# MainDuasRodas.net
KiCad netlist of a schematic drawn in Altium Designer
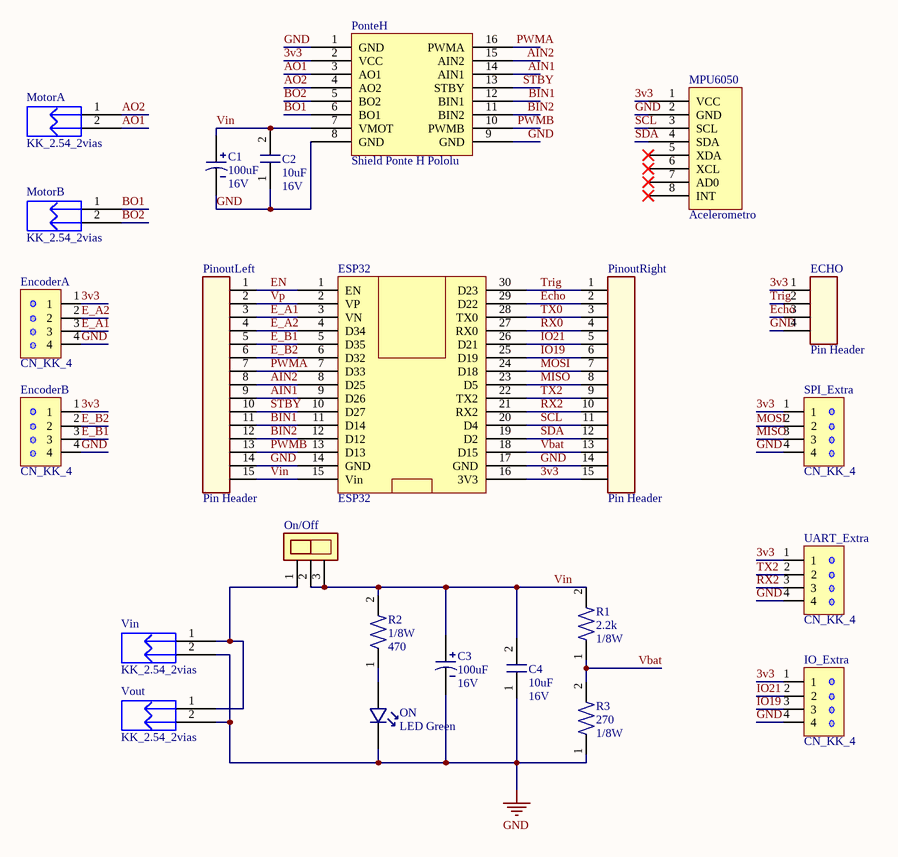
[diagram p0: MainDuasRodas.SchDoc]

(export (version "E")
  (design (tool "Eeschema 10.0.6"))
  (components
    (comp (ref "C1")
      (value "Cap Elec 100uF/16V")
      (footprint "Cap Elec 100uF/16V")
      (description "100µF 16V Aluminum Electrolytic Capacitors Radial")
      (fields (field (name "CAPACITANCE") "100uF") (field (name "VOLTAGE") "16V"))
      (libsource (lib "Capacitor Electrolytic PTH") (part "Cap Elec 100uF/16V"))
    )
    (comp (ref "C2")
      (value "CAP 10uF/16v")
      (footprint "CAP 10uF/16V")
      (description "10µF ±10% 16V Ceramic Capacitor X5R 0805 (2012 Metric)")
      (fields (field (name "CAPACITANCE") "10uF") (field (name "VOLTAGE") "16V"))
      (libsource (lib "Ceramic Capacitors 0805 16V") (part "CAP 10uF/16V"))
    )
    (comp (ref "C3")
      (value "Cap Elec 100uF/16V")
      (footprint "Cap Elec 100uF/16V")
      (description "100µF 16V Aluminum Electrolytic Capacitors Radial")
      (fields (field (name "CAPACITANCE") "100uF") (field (name "VOLTAGE") "16V"))
      (libsource (lib "Capacitor Electrolytic PTH") (part "Cap Elec 100uF/16V"))
    )
    (comp (ref "C4")
      (value "CAP 10uF/16v")
      (footprint "CAP 10uF/16V")
      (description "10µF ±10% 16V Ceramic Capacitor X5R 0805 (2012 Metric)")
      (fields (field (name "CAPACITANCE") "10uF") (field (name "VOLTAGE") "16V"))
      (libsource (lib "Ceramic Capacitors 0805 16V") (part "CAP 10uF/16V"))
    )
    (comp (ref "ECHO")
      (value "Pin Header")
      (footprint "Pin Header 4 Ways")
      (description "Connector Header PTH 0.100\" (2.54mm)")
      (libsource (lib "Connectors") (part "Pin Header 4 ways"))
    )
    (comp (ref "EncoderA")
      (value "CN_KK_4")
      (footprint "CN_KK_4_5045-4")
      (description "KK_4")
      (libsource (lib "") (part "CN_KK_4_1"))
    )
    (comp (ref "EncoderB")
      (value "CN_KK_4")
      (footprint "CN_KK_4_5045-4")
      (description "KK_4")
      (libsource (lib "") (part "CN_KK_4_1"))
    )
    (comp (ref "ESP32")
      (value "ESP32")
      (footprint "DIP30 - duplicate3")
      (libsource (lib "ESP32_NodeMCU") (part "ESP32"))
    )
    (comp (ref "IO_Extra")
      (value "CN_KK_4")
      (footprint "CN_KK_4_5045-4")
      (description "KK_4")
      (libsource (lib "i9Library_Altium") (part "CN_KK_4"))
    )
    (comp (ref "MotorA")
      (value "KK_2.54_2vias")
      (footprint "KK_2VIAS_180º")
      (description "Conector KK 2.54mm 2 vias")
      (libsource (lib "Altium_Library_Brasil") (part "KK_2.54_2vias"))
    )
    (comp (ref "MotorB")
      (value "KK_2.54_2vias")
      (footprint "KK_2VIAS_180º")
      (description "Conector KK 2.54mm 2 vias")
      (libsource (lib "Altium_Library_Brasil") (part "KK_2.54_2vias"))
    )
    (comp (ref "MPU6050")
      (value "Acelerometro")
      (footprint "MPU6050")
      (libsource (lib "MPU6050") (part "MPU6050"))
    )
    (comp (ref "ON")
      (value "LED Green")
      (footprint "LED GREEN PTH STAND")
      (description "Green 527nm LED Indication - Discrete 3.2V Radial")
      (libsource (lib "LEDs") (part "LED Green PTH Stand"))
    )
    (comp (ref "On/Off")
      (value "SS12D00G4")
      (footprint "SS12D00G4")
      (libsource (lib "Buttons & Switches") (part "SS12D00G4"))
    )
    (comp (ref "PinoutLeft")
      (value "Pin Header")
      (footprint "Pin Header 15 Ways")
      (description "Connector Header PTH 0.100\" (2.54mm)")
      (libsource (lib "Connectors") (part "Pin Header 15 ways"))
    )
    (comp (ref "PinoutRight")
      (value "Pin Header")
      (footprint "Pin Header 15 Ways")
      (description "Connector Header PTH 0.100\" (2.54mm)")
      (libsource (lib "") (part "Pin Header 15 ways_1"))
    )
    (comp (ref "PonteH")
      (value "Shield Ponte H Pololu")
      (footprint "SHIELDMD08AR")
      (libsource (lib "md08a2") (part "Md08a"))
    )
    (comp (ref "R1")
      (value "RES 0805")
      (footprint "RES SMD 2.2k OHM 1% 1/8W 0805")
      (description "2.2 kOhms ±1% 0.125W, 1/8W Chip Resistor 0805 (2012 Metric) Moisture Resistant Thick Film")
      (fields (field (name "RESISTENCE") "2.2k") (field (name "POWER") "1/8W"))
      (libsource (lib "Resistors 0805") (part "RES 2.2k 1% 1/8W"))
    )
    (comp (ref "R2")
      (value "RES 0805")
      (footprint "RES SMD 470OHM 1% 1/8W 0805")
      (description "470 Ohms ±1% 0.125W, 1/8W Chip Resistor 0805 (2012 Metric) Moisture Resistant Thick Film")
      (fields (field (name "POWER") "1/8W") (field (name "RESISTENCE") "470"))
      (libsource (lib "Resistors 0805") (part "RES 470 1% 1/8W"))
    )
    (comp (ref "R3")
      (value "RES 0805")
      (footprint "RES SMD 270 OHM 1% 1/8W 0805")
      (description "270Ohms ±1% 0.125W, 1/8W Chip Resistor 0805 (2012 Metric) Moisture Resistant Thick Film")
      (fields (field (name "RESISTENCE") "270") (field (name "POWER") "1/8W"))
      (libsource (lib "Resistors 0805") (part "RES 270 1% 1/8W"))
    )
    (comp (ref "SPI_Extra")
      (value "CN_KK_4")
      (footprint "CN_KK_4_5045-4")
      (description "KK_4")
      (libsource (lib "i9Library_Altium") (part "CN_KK_4"))
    )
    (comp (ref "UART_Extra")
      (value "CN_KK_4")
      (footprint "CN_KK_4_5045-4")
      (description "KK_4")
      (libsource (lib "i9Library_Altium") (part "CN_KK_4"))
    )
    (comp (ref "Vin")
      (value "KK_2.54_2vias")
      (footprint "KK_2VIAS_180º")
      (description "Conector KK 2.54mm 2 vias")
      (libsource (lib "Altium_Library_Brasil") (part "KK_2.54_2vias"))
    )
    (comp (ref "Vout")
      (value "KK_2.54_2vias")
      (footprint "KK_2VIAS_180º")
      (description "Conector KK 2.54mm 2 vias")
      (libsource (lib "Altium_Library_Brasil") (part "KK_2.54_2vias"))
    )
  )
  (nets
    (net (code "1") (name "/3v3") (class "Default")
      (node (ref "ECHO") (pin "1") (pinfunction "1_1") (pintype "passive"))
      (node (ref "ESP32") (pin "16") (pinfunction "3V3_16") (pintype "passive"))
      (node (ref "EncoderA") (pin "1") (pinfunction "1_1") (pintype "passive"))
      (node (ref "EncoderB") (pin "1") (pinfunction "1_1") (pintype "passive"))
      (node (ref "IO_Extra") (pin "1") (pinfunction "1_1") (pintype "passive"))
      (node (ref "MPU6050") (pin "1") (pinfunction "VCC_1") (pintype "passive"))
      (node (ref "PinoutRight") (pin "15") (pinfunction "15_15") (pintype "passive"))
      (node (ref "PonteH") (pin "2") (pinfunction "VCC_2") (pintype "passive"))
      (node (ref "SPI_Extra") (pin "1") (pinfunction "1_1") (pintype "passive"))
      (node (ref "UART_Extra") (pin "1") (pinfunction "1_1") (pintype "passive"))
    )
    (net (code "2") (name "/AIN1") (class "Default")
      (node (ref "ESP32") (pin "9") (pinfunction "D26_9") (pintype "passive"))
      (node (ref "PinoutLeft") (pin "9") (pinfunction "9_9") (pintype "passive"))
      (node (ref "PonteH") (pin "14") (pinfunction "AIN1_14") (pintype "passive"))
    )
    (net (code "3") (name "/AIN2") (class "Default")
      (node (ref "ESP32") (pin "8") (pinfunction "D25_8") (pintype "passive"))
      (node (ref "PinoutLeft") (pin "8") (pinfunction "8_8") (pintype "passive"))
      (node (ref "PonteH") (pin "15") (pinfunction "AIN2_15") (pintype "passive"))
    )
    (net (code "4") (name "/AO1") (class "Default")
      (node (ref "MotorA") (pin "2") (pintype "passive"))
      (node (ref "PonteH") (pin "3") (pinfunction "AO1_3") (pintype "passive"))
    )
    (net (code "5") (name "/AO2") (class "Default")
      (node (ref "MotorA") (pin "1") (pintype "passive"))
      (node (ref "PonteH") (pin "4") (pinfunction "AO2_4") (pintype "passive"))
    )
    (net (code "6") (name "/BIN1") (class "Default")
      (node (ref "ESP32") (pin "11") (pinfunction "D14_11") (pintype "passive"))
      (node (ref "PinoutLeft") (pin "11") (pinfunction "11_11") (pintype "passive"))
      (node (ref "PonteH") (pin "12") (pinfunction "BIN1_12") (pintype "passive"))
    )
    (net (code "7") (name "/BIN2") (class "Default")
      (node (ref "ESP32") (pin "12") (pinfunction "D12_12") (pintype "passive"))
      (node (ref "PinoutLeft") (pin "12") (pinfunction "12_12") (pintype "passive"))
      (node (ref "PonteH") (pin "11") (pinfunction "BIN2_11") (pintype "passive"))
    )
    (net (code "8") (name "/BO1") (class "Default")
      (node (ref "MotorB") (pin "1") (pintype "passive"))
      (node (ref "PonteH") (pin "6") (pinfunction "BO1_6") (pintype "passive"))
    )
    (net (code "9") (name "/BO2") (class "Default")
      (node (ref "MotorB") (pin "2") (pintype "passive"))
      (node (ref "PonteH") (pin "5") (pinfunction "BO2_5") (pintype "passive"))
    )
    (net (code "10") (name "/EN") (class "Default")
      (node (ref "ESP32") (pin "1") (pinfunction "EN_1") (pintype "passive"))
      (node (ref "PinoutLeft") (pin "1") (pinfunction "1_1") (pintype "passive"))
    )
    (net (code "11") (name "/E_A1") (class "Default")
      (node (ref "ESP32") (pin "3") (pinfunction "VN_3") (pintype "passive"))
      (node (ref "EncoderA") (pin "3") (pinfunction "3_3") (pintype "passive"))
      (node (ref "PinoutLeft") (pin "3") (pinfunction "3_3") (pintype "passive"))
    )
    (net (code "12") (name "/E_A2") (class "Default")
      (node (ref "ESP32") (pin "4") (pinfunction "D34_4") (pintype "passive"))
      (node (ref "EncoderA") (pin "2") (pinfunction "2_2") (pintype "passive"))
      (node (ref "PinoutLeft") (pin "4") (pinfunction "4_4") (pintype "passive"))
    )
    (net (code "13") (name "/E_B1") (class "Default")
      (node (ref "ESP32") (pin "5") (pinfunction "D35_5") (pintype "passive"))
      (node (ref "EncoderB") (pin "3") (pinfunction "3_3") (pintype "passive"))
      (node (ref "PinoutLeft") (pin "5") (pinfunction "5_5") (pintype "passive"))
    )
    (net (code "14") (name "/E_B2") (class "Default")
      (node (ref "ESP32") (pin "6") (pinfunction "D32_6") (pintype "passive"))
      (node (ref "EncoderB") (pin "2") (pinfunction "2_2") (pintype "passive"))
      (node (ref "PinoutLeft") (pin "6") (pinfunction "6_6") (pintype "passive"))
    )
    (net (code "15") (name "/Echo") (class "Default")
      (node (ref "ECHO") (pin "3") (pinfunction "3_3") (pintype "passive"))
      (node (ref "ESP32") (pin "29") (pinfunction "D22_29") (pintype "passive"))
      (node (ref "PinoutRight") (pin "2") (pinfunction "2_2") (pintype "passive"))
    )
    (net (code "16") (name "/IO19") (class "Default")
      (node (ref "ESP32") (pin "25") (pinfunction "D19_25") (pintype "passive"))
      (node (ref "IO_Extra") (pin "3") (pinfunction "3_3") (pintype "passive"))
      (node (ref "PinoutRight") (pin "6") (pinfunction "6_6") (pintype "passive"))
    )
    (net (code "17") (name "/IO21") (class "Default")
      (node (ref "ESP32") (pin "26") (pinfunction "D21_26") (pintype "passive"))
      (node (ref "IO_Extra") (pin "2") (pinfunction "2_2") (pintype "passive"))
      (node (ref "PinoutRight") (pin "5") (pinfunction "5_5") (pintype "passive"))
    )
    (net (code "18") (name "/MISO") (class "Default")
      (node (ref "ESP32") (pin "23") (pinfunction "D5_23") (pintype "passive"))
      (node (ref "PinoutRight") (pin "8") (pinfunction "8_8") (pintype "passive"))
      (node (ref "SPI_Extra") (pin "3") (pinfunction "3_3") (pintype "passive"))
    )
    (net (code "19") (name "/MOSI") (class "Default")
      (node (ref "ESP32") (pin "24") (pinfunction "D18_24") (pintype "passive"))
      (node (ref "PinoutRight") (pin "7") (pinfunction "7_7") (pintype "passive"))
      (node (ref "SPI_Extra") (pin "2") (pinfunction "2_2") (pintype "passive"))
    )
    (net (code "20") (name "/PWMA") (class "Default")
      (node (ref "ESP32") (pin "7") (pinfunction "D33_7") (pintype "passive"))
      (node (ref "PinoutLeft") (pin "7") (pinfunction "7_7") (pintype "passive"))
      (node (ref "PonteH") (pin "16") (pinfunction "PWMA_16") (pintype "passive"))
    )
    (net (code "21") (name "/PWMB") (class "Default")
      (node (ref "ESP32") (pin "13") (pinfunction "D13_13") (pintype "passive"))
      (node (ref "PinoutLeft") (pin "13") (pinfunction "13_13") (pintype "passive"))
      (node (ref "PonteH") (pin "10") (pinfunction "PWMB_10") (pintype "passive"))
    )
    (net (code "22") (name "/RX0") (class "Default")
      (node (ref "ESP32") (pin "27") (pinfunction "RX0_27") (pintype "passive"))
      (node (ref "PinoutRight") (pin "4") (pinfunction "4_4") (pintype "passive"))
    )
    (net (code "23") (name "/RX2") (class "Default")
      (node (ref "ESP32") (pin "21") (pinfunction "RX2_21") (pintype "passive"))
      (node (ref "PinoutRight") (pin "10") (pinfunction "10_10") (pintype "passive"))
      (node (ref "UART_Extra") (pin "3") (pinfunction "3_3") (pintype "passive"))
    )
    (net (code "24") (name "/SCL") (class "Default")
      (node (ref "ESP32") (pin "20") (pinfunction "D4_20") (pintype "passive"))
      (node (ref "MPU6050") (pin "3") (pinfunction "SCL_3") (pintype "passive"))
      (node (ref "PinoutRight") (pin "11") (pinfunction "11_11") (pintype "passive"))
    )
    (net (code "25") (name "/SDA") (class "Default")
      (node (ref "ESP32") (pin "19") (pinfunction "D2_19") (pintype "passive"))
      (node (ref "MPU6050") (pin "4") (pinfunction "SDA_4") (pintype "passive"))
      (node (ref "PinoutRight") (pin "12") (pinfunction "12_12") (pintype "passive"))
    )
    (net (code "26") (name "/STBY") (class "Default")
      (node (ref "ESP32") (pin "10") (pinfunction "D27_10") (pintype "passive"))
      (node (ref "PinoutLeft") (pin "10") (pinfunction "10_10") (pintype "passive"))
      (node (ref "PonteH") (pin "13") (pinfunction "STBY_13") (pintype "passive"))
    )
    (net (code "27") (name "/TX0") (class "Default")
      (node (ref "ESP32") (pin "28") (pinfunction "TX0_28") (pintype "passive"))
      (node (ref "PinoutRight") (pin "3") (pinfunction "3_3") (pintype "passive"))
    )
    (net (code "28") (name "/TX2") (class "Default")
      (node (ref "ESP32") (pin "22") (pinfunction "TX2_22") (pintype "passive"))
      (node (ref "PinoutRight") (pin "9") (pinfunction "9_9") (pintype "passive"))
      (node (ref "UART_Extra") (pin "2") (pinfunction "2_2") (pintype "passive"))
    )
    (net (code "29") (name "/Trig") (class "Default")
      (node (ref "ECHO") (pin "2") (pinfunction "2_2") (pintype "passive"))
      (node (ref "ESP32") (pin "30") (pinfunction "D23_30") (pintype "passive"))
      (node (ref "PinoutRight") (pin "1") (pinfunction "1_1") (pintype "passive"))
    )
    (net (code "30") (name "/Vbat") (class "Default")
      (node (ref "ESP32") (pin "18") (pinfunction "D15_18") (pintype "passive"))
      (node (ref "PinoutRight") (pin "13") (pinfunction "13_13") (pintype "passive"))
      (node (ref "R1") (pin "1") (pinfunction "1_1") (pintype "passive"))
      (node (ref "R3") (pin "2") (pinfunction "2_2") (pintype "passive"))
    )
    (net (code "31") (name "/Vin") (class "Default")
      (node (ref "C1") (pin "2") (pinfunction "2_2") (pintype "passive"))
      (node (ref "C2") (pin "2") (pinfunction "2_2") (pintype "passive"))
      (node (ref "C3") (pin "2") (pinfunction "2_2") (pintype "passive"))
      (node (ref "C4") (pin "2") (pinfunction "2_2") (pintype "passive"))
      (node (ref "ESP32") (pin "15") (pinfunction "Vin_15") (pintype "passive"))
      (node (ref "On/Off") (pin "2") (pintype "passive"))
      (node (ref "On/Off") (pin "3") (pintype "passive"))
      (node (ref "PinoutLeft") (pin "15") (pinfunction "15_15") (pintype "passive"))
      (node (ref "PonteH") (pin "7") (pinfunction "VMOT_7") (pintype "passive"))
      (node (ref "R1") (pin "2") (pinfunction "2_2") (pintype "passive"))
      (node (ref "R2") (pin "2") (pinfunction "2_2") (pintype "passive"))
    )
    (net (code "32") (name "/Vp") (class "Default")
      (node (ref "ESP32") (pin "2") (pinfunction "VP_2") (pintype "passive"))
      (node (ref "PinoutLeft") (pin "2") (pinfunction "2_2") (pintype "passive"))
    )
    (net (code "33") (name "GND") (class "Default")
      (node (ref "C1") (pin "1") (pinfunction "1_1") (pintype "passive"))
      (node (ref "C2") (pin "1") (pinfunction "1_1") (pintype "passive"))
      (node (ref "C3") (pin "1") (pinfunction "1_1") (pintype "passive"))
      (node (ref "C4") (pin "1") (pinfunction "1_1") (pintype "passive"))
      (node (ref "ECHO") (pin "4") (pinfunction "4_4") (pintype "passive"))
      (node (ref "ESP32") (pin "14") (pinfunction "GND_14") (pintype "passive"))
      (node (ref "ESP32") (pin "17") (pinfunction "GND_17") (pintype "passive"))
      (node (ref "EncoderA") (pin "4") (pinfunction "4_4") (pintype "passive"))
      (node (ref "EncoderB") (pin "4") (pinfunction "4_4") (pintype "passive"))
      (node (ref "IO_Extra") (pin "4") (pinfunction "4_4") (pintype "passive"))
      (node (ref "MPU6050") (pin "2") (pinfunction "GND_2") (pintype "passive"))
      (node (ref "ON") (pin "K") (pinfunction "K_K") (pintype "passive"))
      (node (ref "PinoutLeft") (pin "14") (pinfunction "14_14") (pintype "passive"))
      (node (ref "PinoutRight") (pin "14") (pinfunction "14_14") (pintype "passive"))
      (node (ref "PonteH") (pin "1") (pinfunction "GND_1") (pintype "passive"))
      (node (ref "PonteH") (pin "8") (pinfunction "GND_8") (pintype "passive"))
      (node (ref "PonteH") (pin "9") (pinfunction "GND_9") (pintype "passive"))
      (node (ref "R3") (pin "1") (pinfunction "1_1") (pintype "passive"))
      (node (ref "SPI_Extra") (pin "4") (pinfunction "4_4") (pintype "passive"))
      (node (ref "UART_Extra") (pin "4") (pinfunction "4_4") (pintype "passive"))
      (node (ref "Vin") (pin "2") (pintype "passive"))
      (node (ref "Vout") (pin "2") (pintype "passive"))
    )
    (net (code "34") (name "Net-(ON-PadA)") (class "Default")
      (node (ref "ON") (pin "A") (pinfunction "A_A") (pintype "passive"))
      (node (ref "R2") (pin "1") (pinfunction "1_1") (pintype "passive"))
    )
    (net (code "35") (name "Net-(On/Off-Pad1)") (class "Default")
      (node (ref "On/Off") (pin "1") (pintype "passive"))
      (node (ref "Vin") (pin "1") (pintype "passive"))
      (node (ref "Vout") (pin "1") (pintype "passive"))
    )
    (net (code "36") (name "unconnected-(MPU6050-AD0-Pad7)") (class "Default")
      (node (ref "MPU6050") (pin "7") (pinfunction "AD0_7") (pintype "passive+no_connect"))
    )
    (net (code "37") (name "unconnected-(MPU6050-INT-Pad8)") (class "Default")
      (node (ref "MPU6050") (pin "8") (pinfunction "INT_8") (pintype "passive+no_connect"))
    )
    (net (code "38") (name "unconnected-(MPU6050-XCL-Pad6)") (class "Default")
      (node (ref "MPU6050") (pin "6") (pinfunction "XCL_6") (pintype "passive+no_connect"))
    )
    (net (code "39") (name "unconnected-(MPU6050-XDA-Pad5)") (class "Default")
      (node (ref "MPU6050") (pin "5") (pinfunction "XDA_5") (pintype "passive+no_connect"))
    )
  )
)
